# STM_DDS_GPIO.net
KiCad netlist of a schematic drawn in Altium Designer
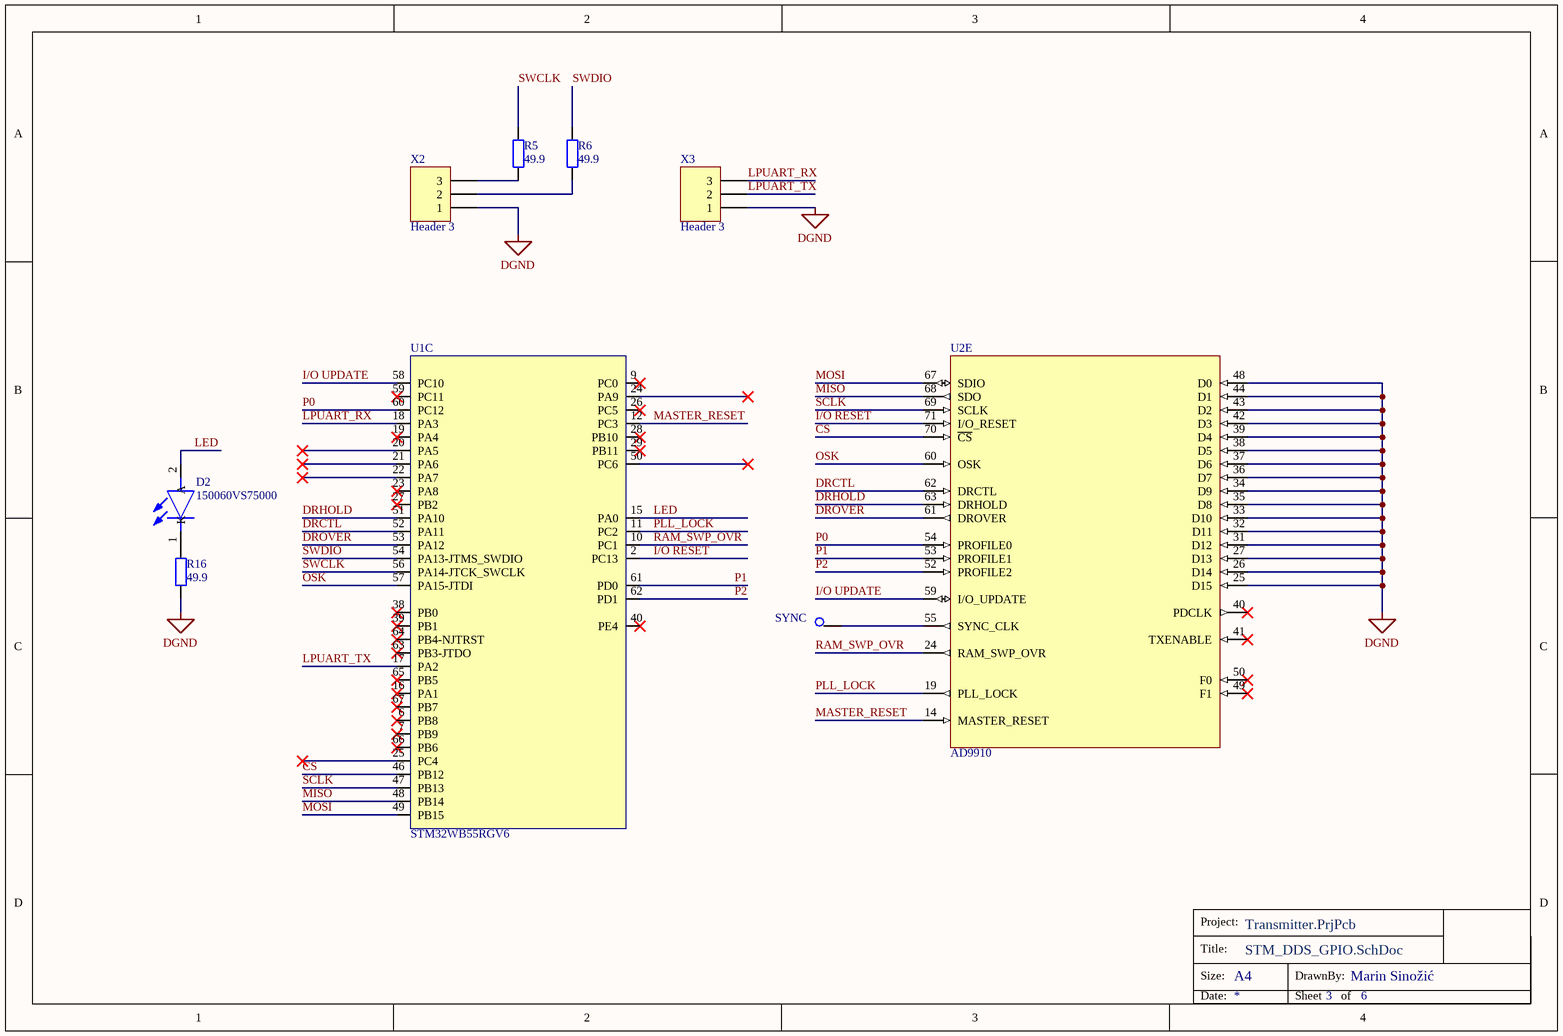
[diagram p0: STM_DDS_GPIO.SchDoc]

(export (version "E")
  (design (tool "Eeschema 10.0.6"))
  (components
    (comp (ref "D2")
      (value "150060VS75000")
      (footprint "0603")
      (description "LED GREEN DIFFUSED 0603 SMD")
      (fields (field (name "MANUFACTURER PART NUMBER") "732-12017-1-ND"))
      (libsource (lib "150060VS75000 (1)") (part "150060VS75000"))
    )
    (comp (ref "R5")
      (value "49.9")
      (footprint "0805")
      (description "RES SMD 49.9 OHM 0.1% 1/10W 0603")
      (fields (field (name "MANUFACTURER PART NUMBER") "P49.9DBCT-ND"))
      (libsource (lib "Miscellaneous Devices") (part "Res2"))
    )
    (comp (ref "R6")
      (value "49.9")
      (footprint "0805")
      (description "RES SMD 49.9 OHM 0.1% 1/10W 0603")
      (fields (field (name "MANUFACTURER PART NUMBER") "P49.9DBCT-ND"))
      (libsource (lib "Miscellaneous Devices") (part "Res2"))
    )
    (comp (ref "R16")
      (value "49.9")
      (footprint "0805")
      (description "RES SMD 49.9 OHM 0.1% 1/10W 0603")
      (fields (field (name "MANUFACTURER PART NUMBER") "P49.9DBCT-ND"))
      (libsource (lib "Miscellaneous Devices") (part "Res2"))
    )
    (comp (ref "SYNC")
      (value "TestPoint")
      (footprint "TP")
      (libsource (lib "Transmitter") (part "TestPoint"))
    )
    (comp (ref "U1")
      (value "STM32WB55RGV6")
      (footprint "VFQFPN69")
      (description "MCU 32-Bit STM32WB55 ARM Cortex M4 RISC 1MB Flash 1.7V to 3.6V 68-Pin VFQFPN Tray")
      (fields (field (name "MANUFACTURER PART NUMBER") "497-18488-ND"))
      (libsource (lib "Transmitter") (part "STM32WB55RGV6"))
    )
    (comp (ref "U2")
      (value "AD9910")
      (footprint "TSQFP50P1600X1600X105_HS-101N")
      (description "ANALOG DEVICES - AD9910BSVZ - Direct Digital Synthesizer, 1 GSPS. 14 Bit, 3.3 V,")
      (fields (field (name "MANUFACTURER PART NUMBER") "505-AD9910BSVZ-ND"))
      (libsource (lib "Transmitter") (part "AD9910BSVZ"))
    )
    (comp (ref "X2")
      (value "Header 3")
      (footprint "HDR1X3")
      (description "Header, 3-Pin")
      (libsource (lib "Miscellaneous Connectors") (part "Header 3"))
    )
    (comp (ref "X3")
      (value "Header 3")
      (footprint "HDR1X3")
      (description "Header, 3-Pin")
      (libsource (lib "Miscellaneous Connectors") (part "Header 3"))
    )
  )
  (nets
    (net (code "1") (name "/DRCTL") (class "Default")
      (node (ref "U1") (pin "52") (pinfunction "PA11_52") (pintype "passive"))
      (node (ref "U2") (pin "62") (pinfunction "DRCTL_62") (pintype "input"))
    )
    (net (code "2") (name "/DRHOLD") (class "Default")
      (node (ref "U1") (pin "51") (pinfunction "PA10_51") (pintype "passive"))
      (node (ref "U2") (pin "63") (pinfunction "DRHOLD_63") (pintype "input"))
    )
    (net (code "3") (name "/DROVER") (class "Default")
      (node (ref "U1") (pin "53") (pinfunction "PA12_53") (pintype "passive"))
      (node (ref "U2") (pin "61") (pinfunction "DROVER_61") (pintype "output"))
    )
    (net (code "4") (name "/I{slash}O RESET") (class "Default")
      (node (ref "U1") (pin "2") (pinfunction "PC13_2") (pintype "passive"))
      (node (ref "U2") (pin "71") (pinfunction "I/O_RESET_71") (pintype "input"))
    )
    (net (code "5") (name "/I{slash}O UPDATE") (class "Default")
      (node (ref "U1") (pin "58") (pinfunction "PC10_58") (pintype "passive"))
      (node (ref "U2") (pin "59") (pinfunction "I/O_UPDATE_59") (pintype "bidirectional"))
    )
    (net (code "6") (name "/LED") (class "Default")
      (node (ref "D2") (pin "2") (pinfunction "A_2") (pintype "bidirectional"))
      (node (ref "U1") (pin "15") (pinfunction "PA0_15") (pintype "passive"))
    )
    (net (code "7") (name "/LPUART_RX") (class "Default")
      (node (ref "U1") (pin "18") (pinfunction "PA3_18") (pintype "passive"))
      (node (ref "X3") (pin "3") (pinfunction "3_3") (pintype "passive"))
    )
    (net (code "8") (name "/LPUART_TX") (class "Default")
      (node (ref "U1") (pin "17") (pinfunction "PA2_17") (pintype "passive"))
      (node (ref "X3") (pin "2") (pinfunction "2_2") (pintype "passive"))
    )
    (net (code "9") (name "/MASTER_RESET") (class "Default")
      (node (ref "U1") (pin "12") (pinfunction "PC3_12") (pintype "passive"))
      (node (ref "U2") (pin "14") (pinfunction "MASTER_RESET_14") (pintype "input"))
    )
    (net (code "10") (name "/MISO") (class "Default")
      (node (ref "U1") (pin "48") (pinfunction "PB14_48") (pintype "passive"))
      (node (ref "U2") (pin "68") (pinfunction "SDO_68") (pintype "output"))
    )
    (net (code "11") (name "/MOSI") (class "Default")
      (node (ref "U1") (pin "49") (pinfunction "PB15_49") (pintype "passive"))
      (node (ref "U2") (pin "67") (pinfunction "SDIO_67") (pintype "bidirectional"))
    )
    (net (code "12") (name "/OSK") (class "Default")
      (node (ref "U1") (pin "57") (pinfunction "PA15-JTDI_57") (pintype "passive"))
      (node (ref "U2") (pin "60") (pinfunction "OSK_60") (pintype "input"))
    )
    (net (code "13") (name "/P0") (class "Default")
      (node (ref "U1") (pin "60") (pinfunction "PC12_60") (pintype "passive"))
      (node (ref "U2") (pin "54") (pinfunction "PROFILE0_54") (pintype "input"))
    )
    (net (code "14") (name "/P1") (class "Default")
      (node (ref "U1") (pin "61") (pinfunction "PD0_61") (pintype "passive"))
      (node (ref "U2") (pin "53") (pinfunction "PROFILE1_53") (pintype "input"))
    )
    (net (code "15") (name "/P2") (class "Default")
      (node (ref "U1") (pin "62") (pinfunction "PD1_62") (pintype "passive"))
      (node (ref "U2") (pin "52") (pinfunction "PROFILE2_52") (pintype "input"))
    )
    (net (code "16") (name "/PLL_LOCK") (class "Default")
      (node (ref "U1") (pin "11") (pinfunction "PC2_11") (pintype "passive"))
      (node (ref "U2") (pin "19") (pinfunction "PLL_LOCK_19") (pintype "output"))
    )
    (net (code "17") (name "/RAM_SWP_OVR") (class "Default")
      (node (ref "U1") (pin "10") (pinfunction "PC1_10") (pintype "passive"))
      (node (ref "U2") (pin "24") (pinfunction "RAM_SWP_OVR_24") (pintype "output"))
    )
    (net (code "18") (name "/SCLK") (class "Default")
      (node (ref "U1") (pin "47") (pinfunction "PB13_47") (pintype "passive"))
      (node (ref "U2") (pin "69") (pinfunction "SCLK_69") (pintype "input"))
    )
    (net (code "19") (name "/SWCLK") (class "Default")
      (node (ref "R5") (pin "1") (pinfunction "1_1") (pintype "passive"))
      (node (ref "U1") (pin "56") (pinfunction "PA14-JTCK_SWCLK_56") (pintype "passive"))
    )
    (net (code "20") (name "/SWDIO") (class "Default")
      (node (ref "R6") (pin "1") (pinfunction "1_1") (pintype "passive"))
      (node (ref "U1") (pin "54") (pinfunction "PA13-JTMS_SWDIO_54") (pintype "passive"))
    )
    (net (code "21") (name "/~{CS}") (class "Default")
      (node (ref "U1") (pin "46") (pinfunction "PB12_46") (pintype "passive"))
      (node (ref "U2") (pin "70") (pinfunction "~{CS}_70") (pintype "input"))
    )
    (net (code "22") (name "DGND") (class "Default")
      (node (ref "R16") (pin "2") (pinfunction "2_2") (pintype "passive"))
      (node (ref "U2") (pin "25") (pinfunction "D15_25") (pintype "input"))
      (node (ref "U2") (pin "26") (pinfunction "D14_26") (pintype "input"))
      (node (ref "U2") (pin "27") (pinfunction "D13_27") (pintype "input"))
      (node (ref "U2") (pin "31") (pinfunction "D12_31") (pintype "input"))
      (node (ref "U2") (pin "32") (pinfunction "D11_32") (pintype "input"))
      (node (ref "U2") (pin "33") (pinfunction "D10_33") (pintype "input"))
      (node (ref "U2") (pin "34") (pinfunction "D9_34") (pintype "input"))
      (node (ref "U2") (pin "35") (pinfunction "D8_35") (pintype "input"))
      (node (ref "U2") (pin "36") (pinfunction "D7_36") (pintype "input"))
      (node (ref "U2") (pin "37") (pinfunction "D6_37") (pintype "input"))
      (node (ref "U2") (pin "38") (pinfunction "D5_38") (pintype "input"))
      (node (ref "U2") (pin "39") (pinfunction "D4_39") (pintype "input"))
      (node (ref "U2") (pin "42") (pinfunction "D3_42") (pintype "input"))
      (node (ref "U2") (pin "43") (pinfunction "D2_43") (pintype "input"))
      (node (ref "U2") (pin "44") (pinfunction "D1_44") (pintype "input"))
      (node (ref "U2") (pin "48") (pinfunction "D0_48") (pintype "input"))
      (node (ref "X2") (pin "1") (pinfunction "1_1") (pintype "passive"))
      (node (ref "X3") (pin "1") (pinfunction "1_1") (pintype "passive"))
    )
    (net (code "23") (name "Net-(D2-K)") (class "Default")
      (node (ref "D2") (pin "1") (pinfunction "K_1") (pintype "bidirectional"))
      (node (ref "R16") (pin "1") (pinfunction "1_1") (pintype "passive"))
    )
    (net (code "24") (name "Net-(R5-Pad2)") (class "Default")
      (node (ref "R5") (pin "2") (pinfunction "2_2") (pintype "passive"))
      (node (ref "X2") (pin "3") (pinfunction "3_3") (pintype "passive"))
    )
    (net (code "25") (name "Net-(R6-Pad2)") (class "Default")
      (node (ref "R6") (pin "2") (pinfunction "2_2") (pintype "passive"))
      (node (ref "X2") (pin "2") (pinfunction "2_2") (pintype "passive"))
    )
    (net (code "26") (name "Net-(U2E-SYNC_CLK)") (class "Default")
      (node (ref "SYNC") (pin "1") (pintype "passive"))
      (node (ref "U2") (pin "55") (pinfunction "SYNC_CLK_55") (pintype "output"))
    )
    (net (code "27") (name "unconnected-(U1C-PA1-Pad16)") (class "Default")
      (node (ref "U1") (pin "16") (pinfunction "PA1_16") (pintype "passive+no_connect"))
    )
    (net (code "28") (name "unconnected-(U1C-PA4-Pad19)") (class "Default")
      (node (ref "U1") (pin "19") (pinfunction "PA4_19") (pintype "passive+no_connect"))
    )
    (net (code "29") (name "unconnected-(U1C-PA5-Pad20)") (class "Default")
      (node (ref "U1") (pin "20") (pinfunction "PA5_20") (pintype "passive+no_connect"))
    )
    (net (code "30") (name "unconnected-(U1C-PA6-Pad21)") (class "Default")
      (node (ref "U1") (pin "21") (pinfunction "PA6_21") (pintype "passive+no_connect"))
    )
    (net (code "31") (name "unconnected-(U1C-PA7-Pad22)") (class "Default")
      (node (ref "U1") (pin "22") (pinfunction "PA7_22") (pintype "passive+no_connect"))
    )
    (net (code "32") (name "unconnected-(U1C-PA8-Pad23)") (class "Default")
      (node (ref "U1") (pin "23") (pinfunction "PA8_23") (pintype "passive+no_connect"))
    )
    (net (code "33") (name "unconnected-(U1C-PA9-Pad24)") (class "Default")
      (node (ref "U1") (pin "24") (pinfunction "PA9_24") (pintype "passive+no_connect"))
    )
    (net (code "34") (name "unconnected-(U1C-PB0-Pad38)") (class "Default")
      (node (ref "U1") (pin "38") (pinfunction "PB0_38") (pintype "passive+no_connect"))
    )
    (net (code "35") (name "unconnected-(U1C-PB1-Pad39)") (class "Default")
      (node (ref "U1") (pin "39") (pinfunction "PB1_39") (pintype "passive+no_connect"))
    )
    (net (code "36") (name "unconnected-(U1C-PB2-Pad27)") (class "Default")
      (node (ref "U1") (pin "27") (pinfunction "PB2_27") (pintype "passive+no_connect"))
    )
    (net (code "37") (name "unconnected-(U1C-PB3-JTDO-Pad63)") (class "Default")
      (node (ref "U1") (pin "63") (pinfunction "PB3-JTDO_63") (pintype "passive+no_connect"))
    )
    (net (code "38") (name "unconnected-(U1C-PB4-NJTRST-Pad64)") (class "Default")
      (node (ref "U1") (pin "64") (pinfunction "PB4-NJTRST_64") (pintype "passive+no_connect"))
    )
    (net (code "39") (name "unconnected-(U1C-PB5-Pad65)") (class "Default")
      (node (ref "U1") (pin "65") (pinfunction "PB5_65") (pintype "passive+no_connect"))
    )
    (net (code "40") (name "unconnected-(U1C-PB6-Pad66)") (class "Default")
      (node (ref "U1") (pin "66") (pinfunction "PB6_66") (pintype "passive+no_connect"))
    )
    (net (code "41") (name "unconnected-(U1C-PB7-Pad67)") (class "Default")
      (node (ref "U1") (pin "67") (pinfunction "PB7_67") (pintype "passive+no_connect"))
    )
    (net (code "42") (name "unconnected-(U1C-PB8-Pad6)") (class "Default")
      (node (ref "U1") (pin "6") (pinfunction "PB8_6") (pintype "passive+no_connect"))
    )
    (net (code "43") (name "unconnected-(U1C-PB9-Pad7)") (class "Default")
      (node (ref "U1") (pin "7") (pinfunction "PB9_7") (pintype "passive+no_connect"))
    )
    (net (code "44") (name "unconnected-(U1C-PB10-Pad28)") (class "Default")
      (node (ref "U1") (pin "28") (pinfunction "PB10_28") (pintype "passive+no_connect"))
    )
    (net (code "45") (name "unconnected-(U1C-PB11-Pad29)") (class "Default")
      (node (ref "U1") (pin "29") (pinfunction "PB11_29") (pintype "passive+no_connect"))
    )
    (net (code "46") (name "unconnected-(U1C-PC0-Pad9)") (class "Default")
      (node (ref "U1") (pin "9") (pinfunction "PC0_9") (pintype "passive+no_connect"))
    )
    (net (code "47") (name "unconnected-(U1C-PC4-Pad25)") (class "Default")
      (node (ref "U1") (pin "25") (pinfunction "PC4_25") (pintype "passive+no_connect"))
    )
    (net (code "48") (name "unconnected-(U1C-PC5-Pad26)") (class "Default")
      (node (ref "U1") (pin "26") (pinfunction "PC5_26") (pintype "passive+no_connect"))
    )
    (net (code "49") (name "unconnected-(U1C-PC6-Pad50)") (class "Default")
      (node (ref "U1") (pin "50") (pinfunction "PC6_50") (pintype "passive+no_connect"))
    )
    (net (code "50") (name "unconnected-(U1C-PC11-Pad59)") (class "Default")
      (node (ref "U1") (pin "59") (pinfunction "PC11_59") (pintype "passive+no_connect"))
    )
    (net (code "51") (name "unconnected-(U1C-PE4-Pad40)") (class "Default")
      (node (ref "U1") (pin "40") (pinfunction "PE4_40") (pintype "passive+no_connect"))
    )
    (net (code "52") (name "unconnected-(U2E-F0-Pad50)") (class "Default")
      (node (ref "U2") (pin "50") (pinfunction "F0_50") (pintype "input+no_connect"))
    )
    (net (code "53") (name "unconnected-(U2E-F1-Pad49)") (class "Default")
      (node (ref "U2") (pin "49") (pinfunction "F1_49") (pintype "input+no_connect"))
    )
    (net (code "54") (name "unconnected-(U2E-PDCLK-Pad40)") (class "Default")
      (node (ref "U2") (pin "40") (pinfunction "PDCLK_40") (pintype "output+no_connect"))
    )
    (net (code "55") (name "unconnected-(U2E-TXENABLE-Pad41)") (class "Default")
      (node (ref "U2") (pin "41") (pinfunction "TXENABLE_41") (pintype "input+no_connect"))
    )
  )
)
